# HID.net
KiCad netlist of a schematic drawn in Altium Designer
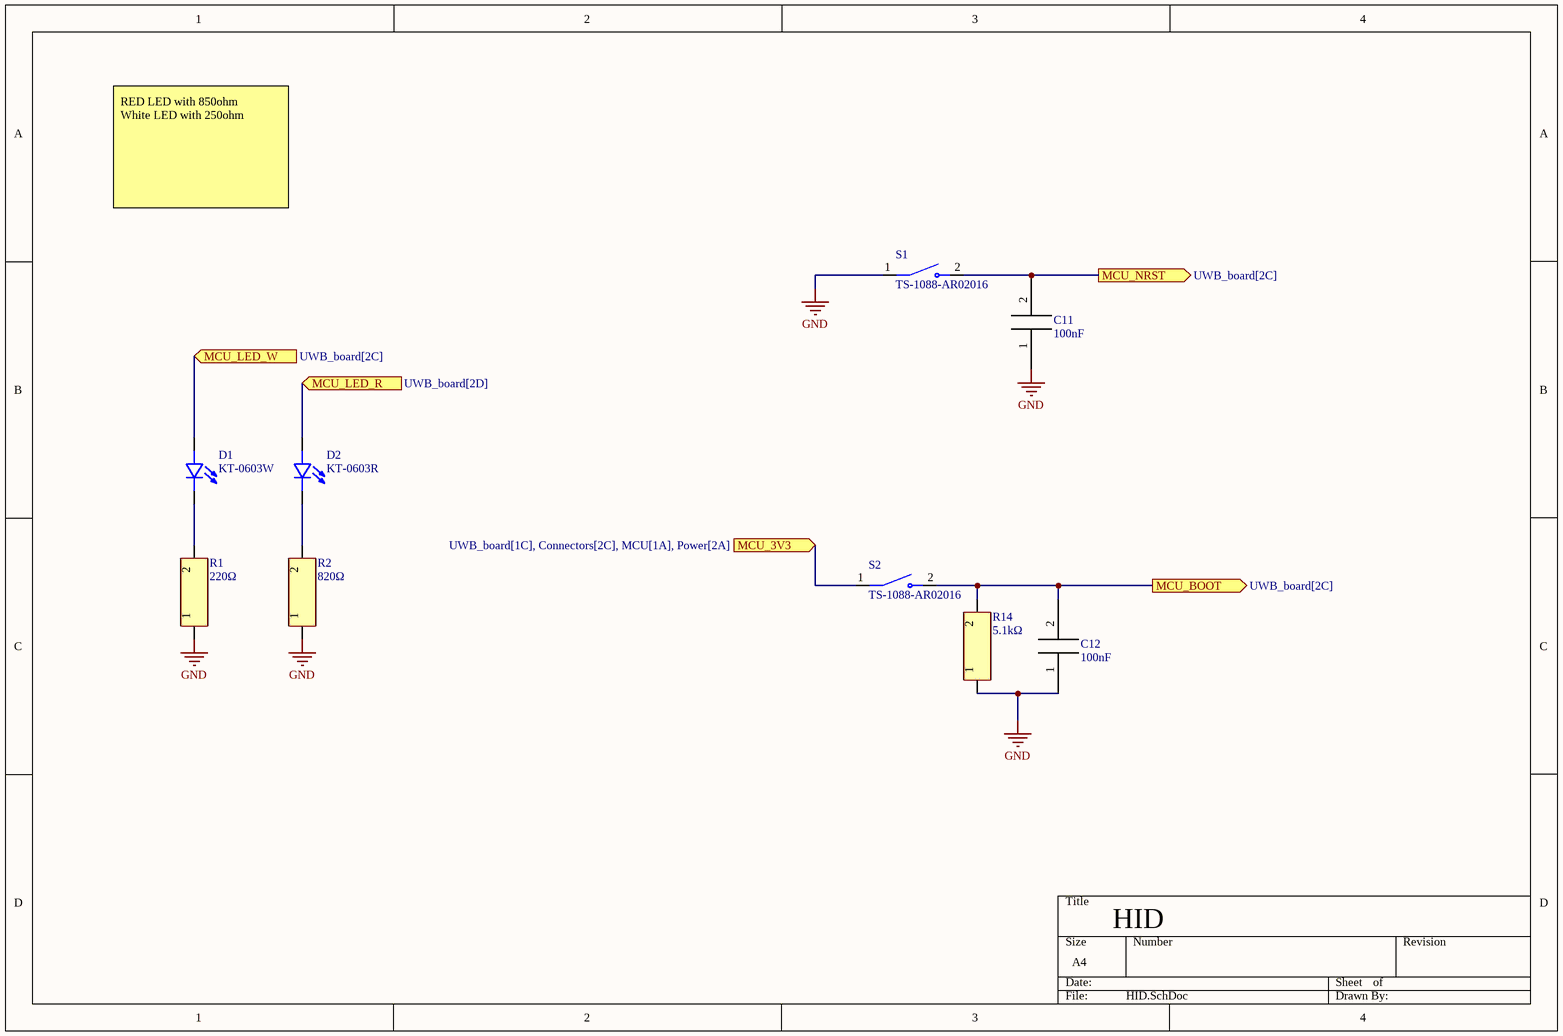
[diagram p0: HID.SchDoc]

(export (version "E")
  (design (tool "Eeschema 10.0.6"))
  (components
    (comp (ref "C11")
      (value "100nF")
      (footprint "0603_cap")
      (description "100nF 50V X7R ±10% 0603 Multilayer Ceramic Capacitors MLCC - SMD/SMT ROHS")
      (fields (field (name "LCSC PART #") "C14663"))
      (libsource (lib "Schlib1") (part "CC0603KRX7R9BB104"))
    )
    (comp (ref "C12")
      (value "100nF")
      (footprint "0603_cap")
      (description "100nF 50V X7R ±10% 0603 Multilayer Ceramic Capacitors MLCC - SMD/SMT ROHS")
      (fields (field (name "LCSC PART #") "C14663"))
      (libsource (lib "Schlib1") (part "CC0603KRX7R9BB104"))
    )
    (comp (ref "D1")
      (value "KT-0603W")
      (footprint "0603_LED")
      (fields (field (name "LCSC PART #") "C2290"))
      (libsource (lib "Schlib1") (part "KT-0603W"))
    )
    (comp (ref "D2")
      (value "KT-0603R")
      (footprint "0603_LED")
      (fields (field (name "LCSC PART #") "C2286"))
      (libsource (lib "Schlib1") (part "KT-0603R"))
    )
    (comp (ref "R1")
      (value "220Ω")
      (footprint "0603_res")
      (fields (field (name "LCSC PART #") "C22962") (field (name "Comment") "220"))
      (libsource (lib "Schlib1") (part "0603WAF2200T5E"))
    )
    (comp (ref "R2")
      (value "820Ω")
      (footprint "0603_res")
      (fields (field (name "LCSC PART #") "C23253") (field (name "Comment") "820"))
      (libsource (lib "Schlib1") (part "0603WAF8200T5E"))
    )
    (comp (ref "R14")
      (value "5.1kΩ")
      (footprint "0603_res")
      (fields (field (name "LCSC PART #") "C23186") (field (name "Comment") "5.1k"))
      (libsource (lib "Schlib1") (part "0603WAF5101T5E"))
    )
    (comp (ref "S1")
      (value "TS-1088-AR02016")
      (footprint "SW_TS-1088-AR02016")
      (fields (field (name "LCSC PART #") "C720477"))
      (libsource (lib "Schlib1") (part "TS-1088-AR02016"))
    )
    (comp (ref "S2")
      (value "TS-1088-AR02016")
      (footprint "SW_TS-1088-AR02016")
      (fields (field (name "LCSC PART #") "C720477"))
      (libsource (lib "Schlib1") (part "TS-1088-AR02016"))
    )
  )
  (nets
    (net (code "1") (name "/MCU_3V3") (class "Default")
      (node (ref "S2") (pin "1") (pinfunction "1_1") (pintype "passive"))
    )
    (net (code "2") (name "/MCU_BOOT") (class "Default")
      (node (ref "C12") (pin "2") (pinfunction "3_2") (pintype "passive"))
      (node (ref "R14") (pin "2") (pinfunction "3_2") (pintype "passive"))
      (node (ref "S2") (pin "2") (pinfunction "2_2") (pintype "passive"))
    )
    (net (code "3") (name "/MCU_LED_R") (class "Default")
      (node (ref "D2") (pin "A") (pinfunction "A_A") (pintype "passive"))
    )
    (net (code "4") (name "/MCU_LED_W") (class "Default")
      (node (ref "D1") (pin "A") (pinfunction "A_A") (pintype "passive"))
    )
    (net (code "5") (name "/MCU_NRST") (class "Default")
      (node (ref "C11") (pin "2") (pinfunction "3_2") (pintype "passive"))
      (node (ref "S1") (pin "2") (pinfunction "2_2") (pintype "passive"))
    )
    (net (code "6") (name "GND") (class "Default")
      (node (ref "C11") (pin "1") (pintype "passive"))
      (node (ref "C12") (pin "1") (pintype "passive"))
      (node (ref "R1") (pin "1") (pinfunction "1_1") (pintype "passive"))
      (node (ref "R14") (pin "1") (pinfunction "1_1") (pintype "passive"))
      (node (ref "R2") (pin "1") (pinfunction "1_1") (pintype "passive"))
      (node (ref "S1") (pin "1") (pinfunction "1_1") (pintype "passive"))
    )
    (net (code "7") (name "Net-(R1-3)") (class "Default")
      (node (ref "D1") (pin "C") (pinfunction "C_C") (pintype "passive"))
      (node (ref "R1") (pin "2") (pinfunction "3_2") (pintype "passive"))
    )
    (net (code "8") (name "Net-(R2-3)") (class "Default")
      (node (ref "D2") (pin "C") (pinfunction "C_C") (pintype "passive"))
      (node (ref "R2") (pin "2") (pinfunction "3_2") (pintype "passive"))
    )
  )
)
